# Shield_WDT.net
KiCad netlist of a schematic drawn in EasyEDA
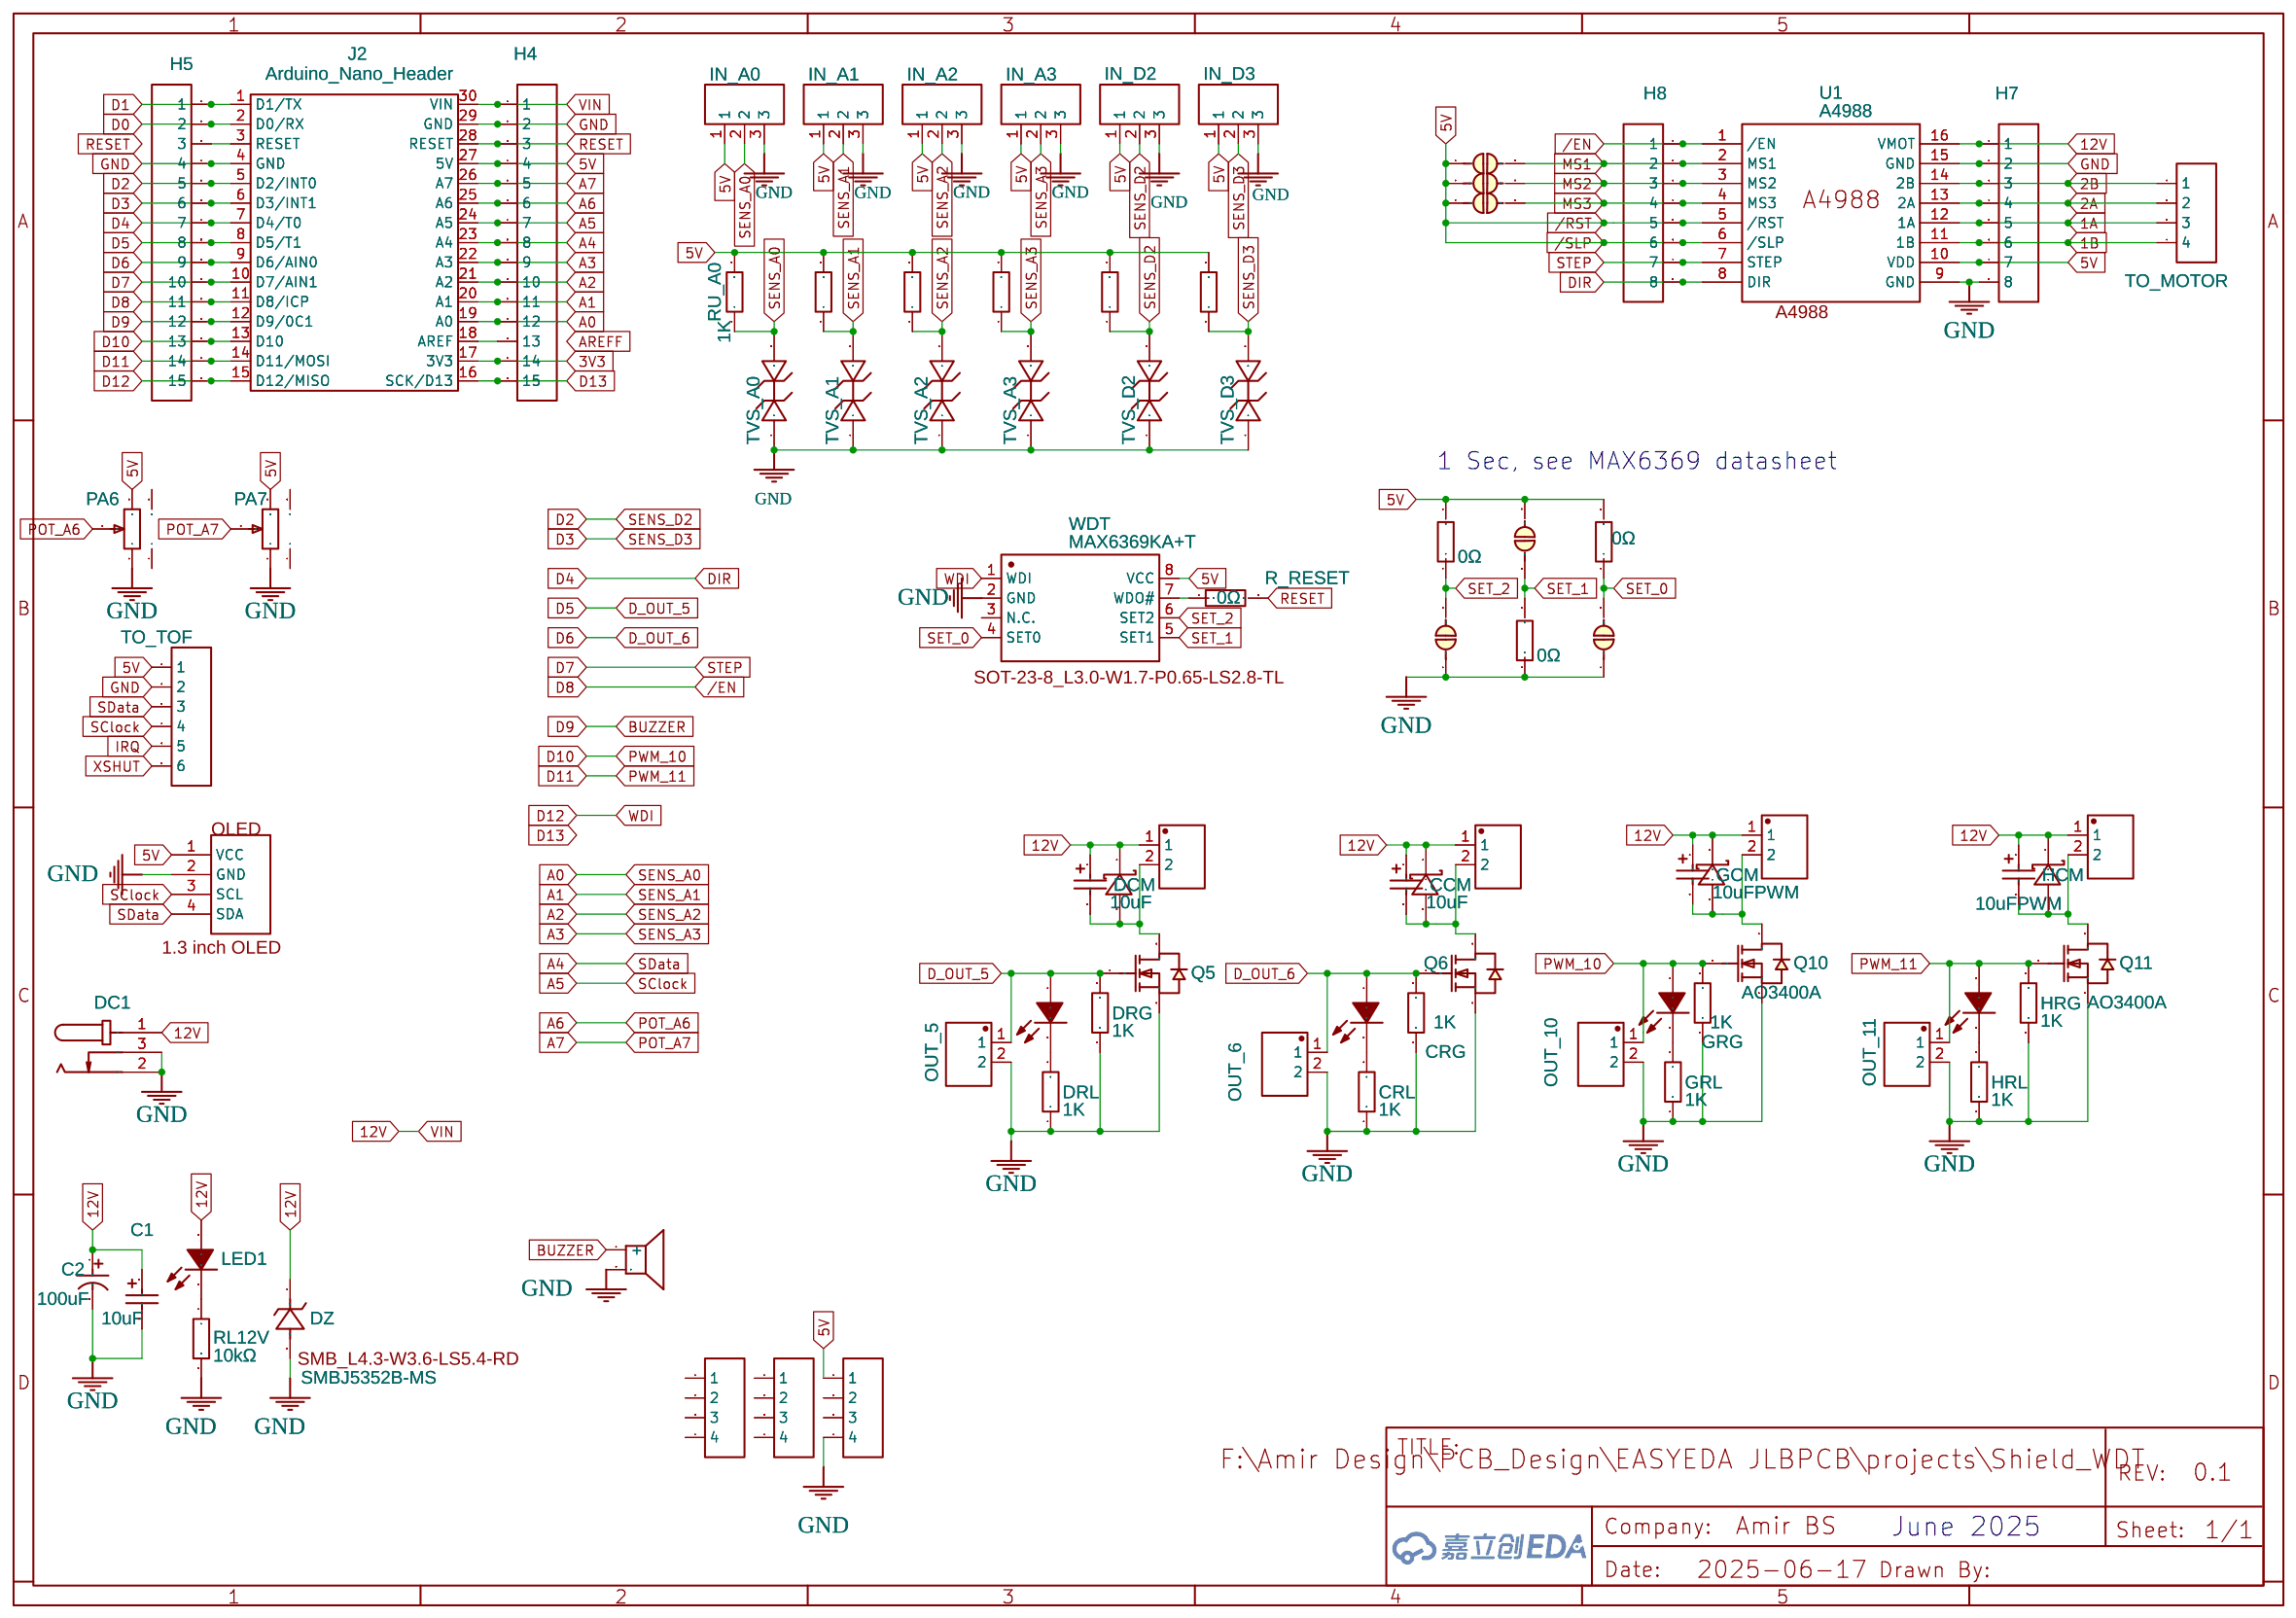
[diagram p0: schematic sheet]

(export (version "E")
  (design (tool "Eeschema 10.0.6"))
  (components
    (comp (ref "BUZZER1") (value "BUZZER-12X9") (libsource (lib "") (part "BUZZER-12X9")))
    (comp (ref "C1")
      (value "10uF")
      (fields (field (name "Manufacturer") "Kyocera AVX"))
      (libsource (lib "") (part "TAJA106K016RNJ_2"))
    )
    (comp (ref "C2")
      (value "100uF")
      (fields (field (name "Manufacturer") "CX(承兴)"))
      (libsource (lib "") (part "100uF 35V 6.3*11"))
    )
    (comp (ref "CCM") (value "10uF") (libsource (lib "") (part "TAJA106K016RNJ_4")))
    (comp (ref "CCON")
      (value "KF2510-2A")
      (fields (field (name "Manufacturer") "BOOMELE"))
      (libsource (lib "") (part "KF2510-2A_4"))
    )
    (comp (ref "CRG")
      (value "1K")
      (fields (field (name "Manufacturer Part") "0603WAF1001T5E") (field (name "Manufacturer") "UniOhm"))
      (libsource (lib "") (part "0603WAF1001T5E_3"))
    )
    (comp (ref "CRL")
      (value "1K")
      (fields (field (name "Manufacturer Part") "0603WAF1001T5E") (field (name "Manufacturer") "UniOhm"))
      (libsource (lib "") (part "0603WAF1001T5E"))
    )
    (comp (ref "D5")
      (value "1N5819WS")
      (fields (field (name "Manufacturer") "Hottech(合科泰)"))
      (libsource (lib "") (part "1N5819WS"))
    )
    (comp (ref "D6")
      (value "1N5819WS")
      (fields (field (name "Manufacturer") "Hottech(合科泰)"))
      (libsource (lib "") (part "1N5819WS"))
    )
    (comp (ref "D10")
      (value "1N5819WS")
      (fields (field (name "Manufacturer") "Hottech(合科泰)"))
      (libsource (lib "") (part "1N5819WS"))
    )
    (comp (ref "D11")
      (value "1N5819WS")
      (fields (field (name "Manufacturer") "Hottech(合科泰)"))
      (libsource (lib "") (part "1N5819WS"))
    )
    (comp (ref "DC1")
      (value "DC")
      (fields (field (name "Manufacturer Part") "DC005-2.0MM") (field (name "Manufacturer") "SOFNG"))
      (libsource (lib "") (part "DC005-2.0MM"))
    )
    (comp (ref "DCM") (value "10uF") (libsource (lib "") (part "TAJA106K016RNJ")))
    (comp (ref "DCON")
      (value "KF2510-2A")
      (fields (field (name "Manufacturer") "BOOMELE"))
      (libsource (lib "") (part "KF2510-2A_3"))
    )
    (comp (ref "DRG")
      (value "1K")
      (fields (field (name "Manufacturer Part") "0603WAF1001T5E") (field (name "Manufacturer") "UniOhm"))
      (libsource (lib "") (part "0603WAF1001T5E_8"))
    )
    (comp (ref "DRL")
      (value "1K")
      (fields (field (name "Manufacturer Part") "0603WAF1001T5E") (field (name "Manufacturer") "UniOhm"))
      (libsource (lib "") (part "0603WAF1001T5E_7"))
    )
    (comp (ref "DZ")
      (value "SMBJ5352B-MS")
      (fields (field (name "Manufacturer") "MSKSEMI(美森科)"))
      (libsource (lib "") (part "SMBJ5352B-MS"))
    )
    (comp (ref "GCM") (value "10uFPWM") (libsource (lib "") (part "TAJA106K016RNJ_1")))
    (comp (ref "GCON")
      (value "KF2510-2A")
      (fields (field (name "Manufacturer") "BOOMELE"))
      (libsource (lib "") (part "KF2510-2A"))
    )
    (comp (ref "GRG")
      (value "1K")
      (fields (field (name "Manufacturer Part") "0603WAF1001T5E") (field (name "Manufacturer") "UniOhm"))
      (libsource (lib "") (part "0603WAF1001T5E_4"))
    )
    (comp (ref "GRL")
      (value "1K")
      (fields (field (name "Manufacturer Part") "0603WAF1001T5E") (field (name "Manufacturer") "UniOhm"))
      (libsource (lib "") (part "0603WAF1001T5E_6"))
    )
    (comp (ref "H1") (value "HDR-F-2.54_1x4") (libsource (lib "") (part "HDR-F-2.54_1x4")))
    (comp (ref "H2") (value "HDR-F-2.54_1x4") (libsource (lib "") (part "HDR-F-2.54_1x4")))
    (comp (ref "H3") (value "HDR-F-2.54_1x4") (libsource (lib "") (part "HDR-F-2.54_1x4")))
    (comp (ref "H4") (value "HDR-F-2.54_1x15") (libsource (lib "") (part "HDR-F-2.54_1x15")))
    (comp (ref "H5") (value "HDR-F-2.54_1x15") (libsource (lib "") (part "HDR-F-2.54_1x15_1")))
    (comp (ref "H7") (value "HDR-F-2.54_1x8") (libsource (lib "") (part "HDR-F-2.54_1x8_1")))
    (comp (ref "H8") (value "HDR-F-2.54_1x8") (libsource (lib "") (part "HDR-F-2.54_1x8")))
    (comp (ref "HCM") (value "10uFPWM") (libsource (lib "") (part "TAJA106K016RNJ_3")))
    (comp (ref "HCON")
      (value "KF2510-2A")
      (fields (field (name "Manufacturer") "BOOMELE"))
      (libsource (lib "") (part "KF2510-2A_1"))
    )
    (comp (ref "HRG")
      (value "1K")
      (fields (field (name "Manufacturer Part") "0603WAF1001T5E") (field (name "Manufacturer") "UniOhm"))
      (libsource (lib "") (part "0603WAF1001T5E_9"))
    )
    (comp (ref "HRL")
      (value "1K")
      (fields (field (name "Manufacturer Part") "0603WAF1001T5E") (field (name "Manufacturer") "UniOhm"))
      (libsource (lib "") (part "0603WAF1001T5E_2"))
    )
    (comp (ref "IN_A0") (value "FK2510") (libsource (lib "") (part "kf2510_3A_1")))
    (comp (ref "IN_A1") (value "FK2510") (libsource (lib "") (part "kf2510_3A_1")))
    (comp (ref "IN_A2") (value "FK2510") (libsource (lib "") (part "kf2510_3A_1")))
    (comp (ref "IN_A3") (value "FK2510") (libsource (lib "") (part "kf2510_3A_1")))
    (comp (ref "IN_D2") (value "FK2510") (libsource (lib "") (part "kf2510_3A")))
    (comp (ref "IN_D3") (value "FK2510") (libsource (lib "") (part "kf2510_3A")))
    (comp (ref "J2") (value "Arduino_Nano_Header") (libsource (lib "") (part "Arduino_Nano_Header")))
    (comp (ref "JP1") (value "JUMPER-SMT_2") (libsource (lib "") (part "JUMPER-SMT_2_1")))
    (comp (ref "JP2") (value "JUMPER-SMT_2") (libsource (lib "") (part "JUMPER-SMT_2_1")))
    (comp (ref "JP3") (value "JUMPER-SMT_2") (libsource (lib "") (part "JUMPER-SMT_2_1")))
    (comp (ref "J_S0") (value "J_SET0") (libsource (lib "") (part "JUMPER-SMT_2")))
    (comp (ref "J_S1") (value "J_SET1") (libsource (lib "") (part "JUMPER-SMT_2")))
    (comp (ref "J_S2") (value "J_SET_2") (libsource (lib "") (part "JUMPER-SMT_2")))
    (comp (ref "LED1")
      (value "KT-0603R")
      (fields (field (name "Manufacturer") "KENTO"))
      (libsource (lib "") (part "KT-0603R"))
    )
    (comp (ref "LED5")
      (value "0603White light_C2290")
      (fields (field (name "Manufacturer") "KENTO"))
      (libsource (lib "") (part "0603White light_C2290"))
    )
    (comp (ref "LED6")
      (value "0603White light_C2290")
      (fields (field (name "Manufacturer") "KENTO"))
      (libsource (lib "") (part "0603White light_C2290"))
    )
    (comp (ref "LED10")
      (value "0603White light_C2290")
      (fields (field (name "Manufacturer") "KENTO"))
      (libsource (lib "") (part "0603White light_C2290"))
    )
    (comp (ref "LED11")
      (value "0603White light_C2290")
      (fields (field (name "Manufacturer") "KENTO"))
      (libsource (lib "") (part "0603White light_C2290"))
    )
    (comp (ref "OLED") (value "OLED_1_3_NO_HOLES") (libsource (lib "") (part "OLED_1_3_NO_HOLES")))
    (comp (ref "OUT_5")
      (value "KF2510-2A")
      (fields (field (name "Manufacturer") "BOOMELE"))
      (libsource (lib "") (part "KF2510-2A_2"))
    )
    (comp (ref "OUT_6")
      (value "KF2510-2A")
      (fields (field (name "Manufacturer") "BOOMELE"))
      (libsource (lib "") (part "KF2510-2A_2"))
    )
    (comp (ref "OUT_10")
      (value "KF2510-2A")
      (fields (field (name "Manufacturer") "BOOMELE"))
      (libsource (lib "") (part "KF2510-2A_2"))
    )
    (comp (ref "OUT_11")
      (value "KF2510-2A")
      (fields (field (name "Manufacturer") "BOOMELE"))
      (libsource (lib "") (part "KF2510-2A_2"))
    )
    (comp (ref "PA6") (value "长柄旋转电位器") (libsource (lib "") (part "长柄旋转电位器")))
    (comp (ref "PA7") (value "长柄旋转电位器") (libsource (lib "") (part "长柄旋转电位器")))
    (comp (ref "Q5")
      (value "AO3400A")
      (fields (field (name "Manufacturer") "AOS"))
      (libsource (lib "") (part "AO3400A"))
    )
    (comp (ref "Q6")
      (value "AO3400A")
      (fields (field (name "Manufacturer") "AOS"))
      (libsource (lib "") (part "AO3400A"))
    )
    (comp (ref "Q10")
      (value "AO3400A")
      (fields (field (name "Manufacturer") "AOS"))
      (libsource (lib "") (part "AO3400A"))
    )
    (comp (ref "Q11")
      (value "AO3400A")
      (fields (field (name "Manufacturer") "AOS"))
      (libsource (lib "") (part "AO3400A"))
    )
    (comp (ref "RL12V")
      (value "10kΩ")
      (fields
        (field (name "Manufacturer Part") "0603WAF1002T5E")
        (field (name "Manufacturer") "UNI-ROYAL(厚声)")
      )
      (libsource (lib "") (part "0603WAF1002T5E"))
    )
    (comp (ref "RU_A0")
      (value "1K")
      (fields (field (name "Manufacturer Part") "0603WAF1001T5E") (field (name "Manufacturer") "UniOhm"))
      (libsource (lib "") (part "0603WAF1001T5E_1"))
    )
    (comp (ref "RU_A1")
      (value "1K")
      (fields (field (name "Manufacturer Part") "0603WAF1001T5E") (field (name "Manufacturer") "UniOhm"))
      (libsource (lib "") (part "0603WAF1001T5E_1"))
    )
    (comp (ref "RU_A2")
      (value "1K")
      (fields (field (name "Manufacturer Part") "0603WAF1001T5E") (field (name "Manufacturer") "UniOhm"))
      (libsource (lib "") (part "0603WAF1001T5E_1"))
    )
    (comp (ref "RU_A3")
      (value "1K")
      (fields (field (name "Manufacturer Part") "0603WAF1001T5E") (field (name "Manufacturer") "UniOhm"))
      (libsource (lib "") (part "0603WAF1001T5E_1"))
    )
    (comp (ref "RU_D2")
      (value "1K")
      (fields (field (name "Manufacturer Part") "0603WAF1001T5E") (field (name "Manufacturer") "UniOhm"))
      (libsource (lib "") (part "0603WAF1001T5E_5"))
    )
    (comp (ref "RU_D3")
      (value "1K")
      (fields (field (name "Manufacturer Part") "0603WAF1001T5E") (field (name "Manufacturer") "UniOhm"))
      (libsource (lib "") (part "0603WAF1001T5E_5"))
    )
    (comp (ref "R_RESET")
      (value "0Ω")
      (fields (field (name "Manufacturer Part") "0402WGF0000TCE") (field (name "Manufacturer") "UniOhm"))
      (libsource (lib "") (part "0402WGF0000TCE_1"))
    )
    (comp (ref "R_S0")
      (value "0Ω")
      (fields (field (name "Manufacturer Part") "0402WGF0000TCE") (field (name "Manufacturer") "UniOhm"))
      (libsource (lib "") (part "0402WGF0000TCE"))
    )
    (comp (ref "R_S1")
      (value "0Ω")
      (fields (field (name "Manufacturer Part") "0402WGF0000TCE") (field (name "Manufacturer") "UniOhm"))
      (libsource (lib "") (part "0402WGF0000TCE"))
    )
    (comp (ref "R_S2")
      (value "0Ω")
      (fields (field (name "Manufacturer Part") "0402WGF0000TCE") (field (name "Manufacturer") "UniOhm"))
      (libsource (lib "") (part "0402WGF0000TCE"))
    )
    (comp (ref "TO_MOTOR") (value "HDR-F-2.54_1x4") (libsource (lib "") (part "HDR-F-2.54_1x4_1")))
    (comp (ref "TO_TOF") (value "HDR-F-2.54_1x6") (libsource (lib "") (part "HDR-F-2.54_1x6")))
    (comp (ref "TVS_A0")
      (value "TVSS5VCES-02GP-J")
      (fields (field (name "Manufacturer") "SINO-IC(光宇睿芯)"))
      (libsource (lib "") (part "TVSS5VCES-02GP-J"))
    )
    (comp (ref "TVS_A1")
      (value "TVSS5VCES-02GP-J")
      (fields (field (name "Manufacturer") "SINO-IC(光宇睿芯)"))
      (libsource (lib "") (part "TVSS5VCES-02GP-J"))
    )
    (comp (ref "TVS_A2")
      (value "TVSS5VCES-02GP-J")
      (fields (field (name "Manufacturer") "SINO-IC(光宇睿芯)"))
      (libsource (lib "") (part "TVSS5VCES-02GP-J"))
    )
    (comp (ref "TVS_A3")
      (value "TVSS5VCES-02GP-J")
      (fields (field (name "Manufacturer") "SINO-IC(光宇睿芯)"))
      (libsource (lib "") (part "TVSS5VCES-02GP-J"))
    )
    (comp (ref "TVS_D2")
      (value "TVSS5VCES-02GP-J")
      (fields (field (name "Manufacturer") "SINO-IC(光宇睿芯)"))
      (libsource (lib "") (part "TVSS5VCES-02GP-J_1"))
    )
    (comp (ref "TVS_D3")
      (value "TVSS5VCES-02GP-J")
      (fields (field (name "Manufacturer") "SINO-IC(光宇睿芯)"))
      (libsource (lib "") (part "TVSS5VCES-02GP-J_1"))
    )
    (comp (ref "U1") (value "A4988") (libsource (lib "") (part "A4988")))
    (comp (ref "WDT")
      (value "MAX6369KA+T")
      (fields (field (name "Manufacturer") "ADI(亚德诺)/MAXIM(美信)"))
      (libsource (lib "") (part "MAX6369KA+T"))
    )
  )
  (nets
    (net (code "1") (name "1A") (class "Default")
      (node (ref "H7") (pin "5") (pinfunction "5_5") (pintype "unspecified"))
      (node (ref "TO_MOTOR") (pin "3") (pinfunction "3_3") (pintype "unspecified"))
      (node (ref "U1") (pin "12") (pinfunction "1A_12") (pintype "unspecified"))
    )
    (net (code "2") (name "1B") (class "Default")
      (node (ref "H7") (pin "6") (pinfunction "6_6") (pintype "unspecified"))
      (node (ref "TO_MOTOR") (pin "4") (pinfunction "4_4") (pintype "unspecified"))
      (node (ref "U1") (pin "11") (pinfunction "1B_11") (pintype "unspecified"))
    )
    (net (code "3") (name "2A") (class "Default")
      (node (ref "H7") (pin "4") (pinfunction "4_4") (pintype "unspecified"))
      (node (ref "TO_MOTOR") (pin "2") (pinfunction "2_2") (pintype "unspecified"))
      (node (ref "U1") (pin "13") (pinfunction "2A_13") (pintype "unspecified"))
    )
    (net (code "4") (name "2B") (class "Default")
      (node (ref "H7") (pin "3") (pinfunction "3_3") (pintype "unspecified"))
      (node (ref "TO_MOTOR") (pin "1") (pinfunction "1_1") (pintype "unspecified"))
      (node (ref "U1") (pin "14") (pinfunction "2B_14") (pintype "unspecified"))
    )
    (net (code "5") (name "3V3") (class "Default")
      (node (ref "H4") (pin "14") (pinfunction "14_14") (pintype "unspecified"))
      (node (ref "J2") (pin "17") (pinfunction "3V3_17") (pintype "unspecified"))
    )
    (net (code "6") (name "5V") (class "Default")
      (node (ref "H3") (pin "1") (pinfunction "1_1") (pintype "unspecified"))
      (node (ref "H4") (pin "4") (pinfunction "4_4") (pintype "unspecified"))
      (node (ref "H7") (pin "7") (pinfunction "7_7") (pintype "unspecified"))
      (node (ref "H8") (pin "5") (pinfunction "5_5") (pintype "unspecified"))
      (node (ref "H8") (pin "6") (pinfunction "6_6") (pintype "unspecified"))
      (node (ref "IN_A0") (pin "1") (pinfunction "1_1") (pintype "unspecified"))
      (node (ref "IN_A1") (pin "1") (pinfunction "1_1") (pintype "unspecified"))
      (node (ref "IN_A2") (pin "1") (pinfunction "1_1") (pintype "unspecified"))
      (node (ref "IN_A3") (pin "1") (pinfunction "1_1") (pintype "unspecified"))
      (node (ref "IN_D2") (pin "1") (pinfunction "1_1") (pintype "unspecified"))
      (node (ref "IN_D3") (pin "1") (pinfunction "1_1") (pintype "unspecified"))
      (node (ref "J2") (pin "27") (pinfunction "5V_27") (pintype "unspecified"))
      (node (ref "JP1") (pin "1") (pinfunction "1_1") (pintype "bidirectional"))
      (node (ref "JP2") (pin "1") (pinfunction "1_1") (pintype "bidirectional"))
      (node (ref "JP3") (pin "1") (pinfunction "1_1") (pintype "bidirectional"))
      (node (ref "J_S1") (pin "2") (pinfunction "2_2") (pintype "bidirectional"))
      (node (ref "OLED") (pin "1") (pinfunction "VCC_1") (pintype "passive"))
      (node (ref "PA6") (pin "3") (pinfunction "3_3") (pintype "input"))
      (node (ref "PA7") (pin "3") (pinfunction "3_3") (pintype "input"))
      (node (ref "RU_A0") (pin "2") (pinfunction "2_2") (pintype "input"))
      (node (ref "RU_A1") (pin "2") (pinfunction "2_2") (pintype "input"))
      (node (ref "RU_A2") (pin "2") (pinfunction "2_2") (pintype "input"))
      (node (ref "RU_A3") (pin "2") (pinfunction "2_2") (pintype "input"))
      (node (ref "RU_D2") (pin "2") (pinfunction "2_2") (pintype "input"))
      (node (ref "RU_D3") (pin "2") (pinfunction "2_2") (pintype "input"))
      (node (ref "R_S0") (pin "2") (pinfunction "2_2") (pintype "input"))
      (node (ref "R_S2") (pin "2") (pinfunction "2_2") (pintype "input"))
      (node (ref "TO_TOF") (pin "1") (pinfunction "1_1") (pintype "input"))
      (node (ref "U1") (pin "10") (pinfunction "VDD_10") (pintype "unspecified"))
      (node (ref "U1") (pin "5") (pinfunction "/RST_5") (pintype "unspecified"))
      (node (ref "U1") (pin "6") (pinfunction "/SLP_6") (pintype "unspecified"))
      (node (ref "WDT") (pin "8") (pinfunction "VCC_8") (pintype "unspecified"))
    )
    (net (code "7") (name "12V") (class "Default")
      (node (ref "C1") (pin "1") (pinfunction "1_1") (pintype "input"))
      (node (ref "C2") (pin "1") (pinfunction "1_1") (pintype "input"))
      (node (ref "CCM") (pin "1") (pinfunction "1_1") (pintype "input"))
      (node (ref "CCON") (pin "1") (pinfunction "1_1") (pintype "unspecified"))
      (node (ref "D10") (pin "1") (pinfunction "K_1") (pintype "unspecified"))
      (node (ref "D11") (pin "1") (pinfunction "K_1") (pintype "unspecified"))
      (node (ref "D5") (pin "1") (pinfunction "K_1") (pintype "unspecified"))
      (node (ref "D6") (pin "1") (pinfunction "K_1") (pintype "unspecified"))
      (node (ref "DC1") (pin "1") (pinfunction "1_1") (pintype "unspecified"))
      (node (ref "DCM") (pin "1") (pinfunction "1_1") (pintype "input"))
      (node (ref "DCON") (pin "1") (pinfunction "1_1") (pintype "unspecified"))
      (node (ref "DZ") (pin "1") (pinfunction "K_1") (pintype "unspecified"))
      (node (ref "GCM") (pin "1") (pinfunction "1_1") (pintype "input"))
      (node (ref "GCON") (pin "1") (pinfunction "1_1") (pintype "unspecified"))
      (node (ref "H4") (pin "1") (pinfunction "1_1") (pintype "unspecified"))
      (node (ref "H7") (pin "1") (pinfunction "1_1") (pintype "unspecified"))
      (node (ref "HCM") (pin "1") (pinfunction "1_1") (pintype "input"))
      (node (ref "HCON") (pin "1") (pinfunction "1_1") (pintype "unspecified"))
      (node (ref "J2") (pin "30") (pinfunction "VIN_30") (pintype "unspecified"))
      (node (ref "LED1") (pin "2") (pinfunction "A_2") (pintype "unspecified"))
      (node (ref "U1") (pin "16") (pinfunction "VMOT_16") (pintype "unspecified"))
    )
    (net (code "8") (name "A0") (class "Default")
      (node (ref "H4") (pin "12") (pinfunction "12_12") (pintype "unspecified"))
      (node (ref "IN_A0") (pin "2") (pinfunction "2_2") (pintype "unspecified"))
      (node (ref "J2") (pin "19") (pinfunction "A0_19") (pintype "unspecified"))
      (node (ref "RU_A0") (pin "1") (pinfunction "1_1") (pintype "input"))
      (node (ref "TVS_A0") (pin "2") (pinfunction "2_2") (pintype "unspecified"))
    )
    (net (code "9") (name "A1") (class "Default")
      (node (ref "H4") (pin "11") (pinfunction "11_11") (pintype "unspecified"))
      (node (ref "IN_A1") (pin "2") (pinfunction "2_2") (pintype "unspecified"))
      (node (ref "J2") (pin "20") (pinfunction "A1_20") (pintype "unspecified"))
      (node (ref "RU_A1") (pin "1") (pinfunction "1_1") (pintype "input"))
      (node (ref "TVS_A1") (pin "2") (pinfunction "2_2") (pintype "unspecified"))
    )
    (net (code "10") (name "A2") (class "Default")
      (node (ref "H4") (pin "10") (pinfunction "10_10") (pintype "unspecified"))
      (node (ref "IN_A2") (pin "2") (pinfunction "2_2") (pintype "unspecified"))
      (node (ref "J2") (pin "21") (pinfunction "A2_21") (pintype "unspecified"))
      (node (ref "RU_A2") (pin "1") (pinfunction "1_1") (pintype "input"))
      (node (ref "TVS_A2") (pin "2") (pinfunction "2_2") (pintype "unspecified"))
    )
    (net (code "11") (name "A3") (class "Default")
      (node (ref "H4") (pin "9") (pinfunction "9_9") (pintype "unspecified"))
      (node (ref "IN_A3") (pin "2") (pinfunction "2_2") (pintype "unspecified"))
      (node (ref "J2") (pin "22") (pinfunction "A3_22") (pintype "unspecified"))
      (node (ref "RU_A3") (pin "1") (pinfunction "1_1") (pintype "input"))
      (node (ref "TVS_A3") (pin "2") (pinfunction "2_2") (pintype "unspecified"))
    )
    (net (code "12") (name "A4") (class "Default")
      (node (ref "H4") (pin "8") (pinfunction "8_8") (pintype "unspecified"))
      (node (ref "J2") (pin "23") (pinfunction "A4_23") (pintype "unspecified"))
      (node (ref "OLED") (pin "4") (pinfunction "SDA_4") (pintype "bidirectional"))
      (node (ref "TO_TOF") (pin "3") (pinfunction "3_3") (pintype "input"))
    )
    (net (code "13") (name "A5") (class "Default")
      (node (ref "H4") (pin "7") (pinfunction "7_7") (pintype "unspecified"))
      (node (ref "J2") (pin "24") (pinfunction "A5_24") (pintype "unspecified"))
      (node (ref "OLED") (pin "3") (pinfunction "SCL_3") (pintype "bidirectional"))
      (node (ref "TO_TOF") (pin "4") (pinfunction "4_4") (pintype "input"))
    )
    (net (code "14") (name "A6") (class "Default")
      (node (ref "H4") (pin "6") (pinfunction "6_6") (pintype "unspecified"))
      (node (ref "J2") (pin "25") (pinfunction "A6_25") (pintype "unspecified"))
      (node (ref "PA6") (pin "2") (pinfunction "2_2") (pintype "input"))
    )
    (net (code "15") (name "A7") (class "Default")
      (node (ref "H4") (pin "5") (pinfunction "5_5") (pintype "unspecified"))
      (node (ref "J2") (pin "26") (pinfunction "A7_26") (pintype "unspecified"))
      (node (ref "PA7") (pin "2") (pinfunction "2_2") (pintype "input"))
    )
    (net (code "17") (name "BUZZER") (class "Default")
      (node (ref "BUZZER1") (pin "1") (pinfunction "+_1") (pintype "unspecified"))
      (node (ref "H5") (pin "12") (pinfunction "12_12") (pintype "unspecified"))
      (node (ref "J2") (pin "12") (pinfunction "D9/0C1_12") (pintype "unspecified"))
    )
    (net (code "18") (name "D0") (class "Default")
      (node (ref "H5") (pin "2") (pinfunction "2_2") (pintype "unspecified"))
      (node (ref "J2") (pin "2") (pinfunction "D0/RX_2") (pintype "unspecified"))
    )
    (net (code "19") (name "D1") (class "Default")
      (node (ref "H5") (pin "1") (pinfunction "1_1") (pintype "unspecified"))
      (node (ref "J2") (pin "1") (pinfunction "D1/TX_1") (pintype "unspecified"))
    )
    (net (code "20") (name "D2") (class "Default")
      (node (ref "H5") (pin "5") (pinfunction "5_5") (pintype "unspecified"))
      (node (ref "IN_D2") (pin "2") (pinfunction "2_2") (pintype "unspecified"))
      (node (ref "J2") (pin "5") (pinfunction "D2/INT0_5") (pintype "unspecified"))
      (node (ref "RU_D2") (pin "1") (pinfunction "1_1") (pintype "input"))
      (node (ref "TVS_D2") (pin "2") (pinfunction "2_2") (pintype "unspecified"))
    )
    (net (code "21") (name "D3") (class "Default")
      (node (ref "H5") (pin "6") (pinfunction "6_6") (pintype "unspecified"))
      (node (ref "IN_D3") (pin "2") (pinfunction "2_2") (pintype "unspecified"))
      (node (ref "J2") (pin "6") (pinfunction "D3/INT1_6") (pintype "unspecified"))
      (node (ref "RU_D3") (pin "1") (pinfunction "1_1") (pintype "input"))
      (node (ref "TVS_D3") (pin "2") (pinfunction "2_2") (pintype "unspecified"))
    )
    (net (code "22") (name "D4") (class "Default")
      (node (ref "H5") (pin "7") (pinfunction "7_7") (pintype "unspecified"))
      (node (ref "H8") (pin "8") (pinfunction "8_8") (pintype "unspecified"))
      (node (ref "J2") (pin "7") (pinfunction "D4/T0_7") (pintype "unspecified"))
      (node (ref "U1") (pin "8") (pinfunction "DIR_8") (pintype "unspecified"))
    )
    (net (code "23") (name "D5") (class "Default")
      (node (ref "DRG") (pin "2") (pinfunction "2_2") (pintype "input"))
      (node (ref "H5") (pin "8") (pinfunction "8_8") (pintype "unspecified"))
      (node (ref "J2") (pin "8") (pinfunction "D5/T1_8") (pintype "unspecified"))
      (node (ref "LED5") (pin "1") (pinfunction "A_1") (pintype "unspecified"))
      (node (ref "OUT_5") (pin "1") (pinfunction "1_1") (pintype "unspecified"))
      (node (ref "Q5") (pin "1") (pinfunction "G_1") (pintype "unspecified"))
    )
    (net (code "24") (name "D6") (class "Default")
      (node (ref "CRG") (pin "2") (pinfunction "2_2") (pintype "input"))
      (node (ref "H5") (pin "9") (pinfunction "9_9") (pintype "unspecified"))
      (node (ref "J2") (pin "9") (pinfunction "D6/AIN0_9") (pintype "unspecified"))
      (node (ref "LED6") (pin "1") (pinfunction "A_1") (pintype "unspecified"))
      (node (ref "OUT_6") (pin "1") (pinfunction "1_1") (pintype "unspecified"))
      (node (ref "Q6") (pin "1") (pinfunction "G_1") (pintype "unspecified"))
    )
    (net (code "25") (name "D7") (class "Default")
      (node (ref "H5") (pin "10") (pinfunction "10_10") (pintype "unspecified"))
      (node (ref "H8") (pin "7") (pinfunction "7_7") (pintype "unspecified"))
      (node (ref "J2") (pin "10") (pinfunction "D7/AIN1_10") (pintype "unspecified"))
      (node (ref "U1") (pin "7") (pinfunction "STEP_7") (pintype "unspecified"))
    )
    (net (code "26") (name "D8") (class "Default")
      (node (ref "H5") (pin "11") (pinfunction "11_11") (pintype "unspecified"))
      (node (ref "H8") (pin "1") (pinfunction "1_1") (pintype "unspecified"))
      (node (ref "J2") (pin "11") (pinfunction "D8/ICP_11") (pintype "unspecified"))
      (node (ref "U1") (pin "1") (pinfunction "/EN_1") (pintype "unspecified"))
    )
    (net (code "27") (name "D10") (class "Default")
      (node (ref "GRG") (pin "2") (pinfunction "2_2") (pintype "input"))
      (node (ref "H5") (pin "13") (pinfunction "13_13") (pintype "unspecified"))
      (node (ref "J2") (pin "13") (pinfunction "D10_13") (pintype "unspecified"))
      (node (ref "LED10") (pin "1") (pinfunction "A_1") (pintype "unspecified"))
      (node (ref "OUT_10") (pin "1") (pinfunction "1_1") (pintype "unspecified"))
      (node (ref "Q10") (pin "1") (pinfunction "G_1") (pintype "unspecified"))
    )
    (net (code "28") (name "D11") (class "Default")
      (node (ref "H5") (pin "14") (pinfunction "14_14") (pintype "unspecified"))
      (node (ref "HRG") (pin "2") (pinfunction "2_2") (pintype "input"))
      (node (ref "J2") (pin "14") (pinfunction "D11/MOSI_14") (pintype "unspecified"))
      (node (ref "LED11") (pin "1") (pinfunction "A_1") (pintype "unspecified"))
      (node (ref "OUT_11") (pin "1") (pinfunction "1_1") (pintype "unspecified"))
      (node (ref "Q11") (pin "1") (pinfunction "G_1") (pintype "unspecified"))
    )
    (net (code "29") (name "D12") (class "Default")
      (node (ref "H5") (pin "15") (pinfunction "15_15") (pintype "unspecified"))
      (node (ref "J2") (pin "15") (pinfunction "D12/MISO_15") (pintype "unspecified"))
      (node (ref "WDT") (pin "1") (pinfunction "WDI_1") (pintype "unspecified"))
    )
    (net (code "30") (name "D13") (class "Default")
      (node (ref "H4") (pin "15") (pinfunction "15_15") (pintype "unspecified"))
      (node (ref "J2") (pin "16") (pinfunction "SCK/D13_16") (pintype "unspecified"))
    )
    (net (code "31") (name "GND") (class "Default")
      (node (ref "BUZZER1") (pin "2") (pinfunction "2_2") (pintype "unspecified"))
      (node (ref "C1") (pin "2") (pinfunction "2_2") (pintype "input"))
      (node (ref "C2") (pin "2") (pinfunction "2_2") (pintype "input"))
      (node (ref "CRG") (pin "1") (pinfunction "1_1") (pintype "input"))
      (node (ref "CRL") (pin "1") (pinfunction "1_1") (pintype "input"))
      (node (ref "DC1") (pin "2") (pinfunction "2_2") (pintype "unspecified"))
      (node (ref "DC1") (pin "3") (pinfunction "3_3") (pintype "unspecified"))
      (node (ref "DRG") (pin "1") (pinfunction "1_1") (pintype "input"))
      (node (ref "DRL") (pin "1") (pinfunction "1_1") (pintype "input"))
      (node (ref "DZ") (pin "2") (pinfunction "A_2") (pintype "unspecified"))
      (node (ref "GRG") (pin "1") (pinfunction "1_1") (pintype "input"))
      (node (ref "GRL") (pin "1") (pinfunction "1_1") (pintype "input"))
      (node (ref "H3") (pin "4") (pinfunction "4_4") (pintype "unspecified"))
      (node (ref "H4") (pin "2") (pinfunction "2_2") (pintype "unspecified"))
      (node (ref "H5") (pin "4") (pinfunction "4_4") (pintype "unspecified"))
      (node (ref "H7") (pin "2") (pinfunction "2_2") (pintype "unspecified"))
      (node (ref "H7") (pin "8") (pinfunction "8_8") (pintype "unspecified"))
      (node (ref "HRG") (pin "1") (pinfunction "1_1") (pintype "input"))
      (node (ref "HRL") (pin "1") (pinfunction "1_1") (pintype "input"))
      (node (ref "IN_A0") (pin "3") (pinfunction "3_3") (pintype "unspecified"))
      (node (ref "IN_A1") (pin "3") (pinfunction "3_3") (pintype "unspecified"))
      (node (ref "IN_A2") (pin "3") (pinfunction "3_3") (pintype "unspecified"))
      (node (ref "IN_A3") (pin "3") (pinfunction "3_3") (pintype "unspecified"))
      (node (ref "IN_D2") (pin "3") (pinfunction "3_3") (pintype "unspecified"))
      (node (ref "IN_D3") (pin "3") (pinfunction "3_3") (pintype "unspecified"))
      (node (ref "J2") (pin "29") (pinfunction "GND_29") (pintype "unspecified"))
      (node (ref "J2") (pin "4") (pinfunction "GND_4") (pintype "unspecified"))
      (node (ref "J_S0") (pin "1") (pinfunction "1_1") (pintype "bidirectional"))
      (node (ref "J_S2") (pin "1") (pinfunction "1_1") (pintype "bidirectional"))
      (node (ref "OLED") (pin "2") (pinfunction "GND_2") (pintype "passive"))
      (node (ref "OUT_10") (pin "2") (pinfunction "2_2") (pintype "unspecified"))
      (node (ref "OUT_11") (pin "2") (pinfunction "2_2") (pintype "unspecified"))
      (node (ref "OUT_5") (pin "2") (pinfunction "2_2") (pintype "unspecified"))
      (node (ref "OUT_6") (pin "2") (pinfunction "2_2") (pintype "unspecified"))
      (node (ref "PA6") (pin "1") (pinfunction "1_1") (pintype "input"))
      (node (ref "PA7") (pin "1") (pinfunction "1_1") (pintype "input"))
      (node (ref "Q10") (pin "2") (pinfunction "S_2") (pintype "unspecified"))
      (node (ref "Q11") (pin "2") (pinfunction "S_2") (pintype "unspecified"))
      (node (ref "Q5") (pin "2") (pinfunction "S_2") (pintype "unspecified"))
      (node (ref "Q6") (pin "2") (pinfunction "S_2") (pintype "unspecified"))
      (node (ref "RL12V") (pin "2") (pinfunction "2_2") (pintype "input"))
      (node (ref "R_S1") (pin "1") (pinfunction "1_1") (pintype "input"))
      (node (ref "TO_TOF") (pin "2") (pinfunction "2_2") (pintype "input"))
      (node (ref "TVS_A0") (pin "1") (pinfunction "1_1") (pintype "unspecified"))
      (node (ref "TVS_A1") (pin "1") (pinfunction "1_1") (pintype "unspecified"))
      (node (ref "TVS_A2") (pin "1") (pinfunction "1_1") (pintype "unspecified"))
      (node (ref "TVS_A3") (pin "1") (pinfunction "1_1") (pintype "unspecified"))
      (node (ref "TVS_D2") (pin "1") (pinfunction "1_1") (pintype "unspecified"))
      (node (ref "TVS_D3") (pin "1") (pinfunction "1_1") (pintype "unspecified"))
      (node (ref "U1") (pin "15") (pinfunction "GND_15") (pintype "unspecified"))
      (node (ref "U1") (pin "9") (pinfunction "GND_9") (pintype "unspecified"))
      (node (ref "WDT") (pin "2") (pinfunction "GND_2") (pintype "unspecified"))
    )
    (net (code "32") (name "IRQ") (class "Default")
      (node (ref "TO_TOF") (pin "5") (pinfunction "5_5") (pintype "input"))
    )
    (net (code "33") (name "MS1") (class "Default")
      (node (ref "H8") (pin "2") (pinfunction "2_2") (pintype "unspecified"))
      (node (ref "JP1") (pin "2") (pinfunction "2_2") (pintype "bidirectional"))
      (node (ref "U1") (pin "2") (pinfunction "MS1_2") (pintype "unspecified"))
    )
    (net (code "34") (name "MS2") (class "Default")
      (node (ref "H8") (pin "3") (pinfunction "3_3") (pintype "unspecified"))
      (node (ref "JP2") (pin "2") (pinfunction "2_2") (pintype "bidirectional"))
      (node (ref "U1") (pin "3") (pinfunction "MS2_3") (pintype "unspecified"))
    )
    (net (code "35") (name "MS3") (class "Default")
      (node (ref "H8") (pin "4") (pinfunction "4_4") (pintype "unspecified"))
      (node (ref "JP3") (pin "2") (pinfunction "2_2") (pintype "bidirectional"))
      (node (ref "U1") (pin "4") (pinfunction "MS3_4") (pintype "unspecified"))
    )
    (net (code "36") (name "Net-(D5-A)") (class "Default")
      (node (ref "D5") (pin "2") (pinfunction "A_2") (pintype "unspecified"))
      (node (ref "DCM") (pin "2") (pinfunction "2_2") (pintype "input"))
      (node (ref "DCON") (pin "2") (pinfunction "2_2") (pintype "unspecified"))
      (node (ref "Q5") (pin "3") (pinfunction "D_3") (pintype "unspecified"))
    )
    (net (code "37") (name "Net-(D6-A)") (class "Default")
      (node (ref "CCM") (pin "2") (pinfunction "2_2") (pintype "input"))
      (node (ref "CCON") (pin "2") (pinfunction "2_2") (pintype "unspecified"))
      (node (ref "D6") (pin "2") (pinfunction "A_2") (pintype "unspecified"))
      (node (ref "Q6") (pin "3") (pinfunction "D_3") (pintype "unspecified"))
    )
    (net (code "38") (name "Net-(D10-A)") (class "Default")
      (node (ref "D10") (pin "2") (pinfunction "A_2") (pintype "unspecified"))
      (node (ref "GCM") (pin "2") (pinfunction "2_2") (pintype "input"))
      (node (ref "GCON") (pin "2") (pinfunction "2_2") (pintype "unspecified"))
      (node (ref "Q10") (pin "3") (pinfunction "D_3") (pintype "unspecified"))
    )
    (net (code "39") (name "Net-(D11-A)") (class "Default")
      (node (ref "D11") (pin "2") (pinfunction "A_2") (pintype "unspecified"))
      (node (ref "HCM") (pin "2") (pinfunction "2_2") (pintype "input"))
      (node (ref "HCON") (pin "2") (pinfunction "2_2") (pintype "unspecified"))
      (node (ref "Q11") (pin "3") (pinfunction "D_3") (pintype "unspecified"))
    )
    (net (code "40") (name "Net-(H5-Pad3)") (class "Default")
      (node (ref "H5") (pin "3") (pinfunction "3_3") (pintype "unspecified"))
      (node (ref "J2") (pin "3") (pinfunction "RESET_3") (pintype "unspecified"))
    )
    (net (code "41") (name "Net-(J2-AREF)") (class "Default")
      (node (ref "H4") (pin "13") (pinfunction "13_13") (pintype "unspecified"))
      (node (ref "J2") (pin "18") (pinfunction "AREF_18") (pintype "unspecified"))
    )
    (net (code "42") (name "Net-(LED1-K)") (class "Default")
      (node (ref "LED1") (pin "1") (pinfunction "K_1") (pintype "unspecified"))
      (node (ref "RL12V") (pin "1") (pinfunction "1_1") (pintype "input"))
    )
    (net (code "43") (name "Net-(LED5-K)") (class "Default")
      (node (ref "DRL") (pin "2") (pinfunction "2_2") (pintype "input"))
      (node (ref "LED5") (pin "2") (pinfunction "K_2") (pintype "unspecified"))
    )
    (net (code "44") (name "Net-(LED6-K)") (class "Default")
      (node (ref "CRL") (pin "2") (pinfunction "2_2") (pintype "input"))
      (node (ref "LED6") (pin "2") (pinfunction "K_2") (pintype "unspecified"))
    )
    (net (code "45") (name "Net-(LED10-K)") (class "Default")
      (node (ref "GRL") (pin "2") (pinfunction "2_2") (pintype "input"))
      (node (ref "LED10") (pin "2") (pinfunction "K_2") (pintype "unspecified"))
    )
    (net (code "46") (name "Net-(LED11-K)") (class "Default")
      (node (ref "HRL") (pin "2") (pinfunction "2_2") (pintype "input"))
      (node (ref "LED11") (pin "2") (pinfunction "K_2") (pintype "unspecified"))
    )
    (net (code "47") (name "Net-(WDT-WDO#)") (class "Default")
      (node (ref "R_RESET") (pin "1") (pinfunction "1_1") (pintype "input"))
      (node (ref "WDT") (pin "7") (pinfunction "WDO#_7") (pintype "unspecified"))
    )
    (net (code "48") (name "RESET") (class "Default")
      (node (ref "H4") (pin "3") (pinfunction "3_3") (pintype "unspecified"))
      (node (ref "J2") (pin "28") (pinfunction "RESET_28") (pintype "unspecified"))
      (node (ref "R_RESET") (pin "2") (pinfunction "2_2") (pintype "input"))
    )
    (net (code "49") (name "SET_0") (class "Default")
      (node (ref "J_S0") (pin "2") (pinfunction "2_2") (pintype "bidirectional"))
      (node (ref "R_S0") (pin "1") (pinfunction "1_1") (pintype "input"))
      (node (ref "WDT") (pin "4") (pinfunction "SET0_4") (pintype "unspecified"))
    )
    (net (code "50") (name "SET_1") (class "Default")
      (node (ref "J_S1") (pin "1") (pinfunction "1_1") (pintype "bidirectional"))
      (node (ref "R_S1") (pin "2") (pinfunction "2_2") (pintype "input"))
      (node (ref "WDT") (pin "5") (pinfunction "SET1_5") (pintype "unspecified"))
    )
    (net (code "51") (name "SET_2") (class "Default")
      (node (ref "J_S2") (pin "2") (pinfunction "2_2") (pintype "bidirectional"))
      (node (ref "R_S2") (pin "1") (pinfunction "1_1") (pintype "input"))
      (node (ref "WDT") (pin "6") (pinfunction "SET2_6") (pintype "unspecified"))
    )
    (net (code "52") (name "XSHUT") (class "Default")
      (node (ref "TO_TOF") (pin "6") (pinfunction "6_6") (pintype "input"))
    )
    (net (code "53") (name "unconnected-(H1-Pad1)") (class "Default")
      (node (ref "H1") (pin "1") (pinfunction "1_1") (pintype "unspecified"))
    )
    (net (code "54") (name "unconnected-(H1-Pad2)") (class "Default")
      (node (ref "H1") (pin "2") (pinfunction "2_2") (pintype "unspecified"))
    )
    (net (code "55") (name "unconnected-(H1-Pad3)") (class "Default")
      (node (ref "H1") (pin "3") (pinfunction "3_3") (pintype "unspecified"))
    )
    (net (code "56") (name "unconnected-(H1-Pad4)") (class "Default")
      (node (ref "H1") (pin "4") (pinfunction "4_4") (pintype "unspecified"))
    )
    (net (code "57") (name "unconnected-(H2-Pad1)") (class "Default")
      (node (ref "H2") (pin "1") (pinfunction "1_1") (pintype "unspecified"))
    )
    (net (code "58") (name "unconnected-(H2-Pad2)") (class "Default")
      (node (ref "H2") (pin "2") (pinfunction "2_2") (pintype "unspecified"))
    )
    (net (code "59") (name "unconnected-(H2-Pad3)") (class "Default")
      (node (ref "H2") (pin "3") (pinfunction "3_3") (pintype "unspecified"))
    )
    (net (code "60") (name "unconnected-(H2-Pad4)") (class "Default")
      (node (ref "H2") (pin "4") (pinfunction "4_4") (pintype "unspecified"))
    )
    (net (code "61") (name "unconnected-(H3-Pad2)") (class "Default")
      (node (ref "H3") (pin "2") (pinfunction "2_2") (pintype "unspecified"))
    )
    (net (code "62") (name "unconnected-(H3-Pad3)") (class "Default")
      (node (ref "H3") (pin "3") (pinfunction "3_3") (pintype "unspecified"))
    )
    (net (code "63") (name "unconnected-(PA6-Pad4)") (class "Default")
      (node (ref "PA6") (pin "4") (pinfunction "4_4") (pintype "input"))
    )
    (net (code "64") (name "unconnected-(PA6-Pad5)") (class "Default")
      (node (ref "PA6") (pin "5") (pinfunction "5_5") (pintype "input"))
    )
    (net (code "65") (name "unconnected-(PA7-Pad4)") (class "Default")
      (node (ref "PA7") (pin "4") (pinfunction "4_4") (pintype "input"))
    )
    (net (code "66") (name "unconnected-(PA7-Pad5)") (class "Default")
      (node (ref "PA7") (pin "5") (pinfunction "5_5") (pintype "input"))
    )
    (net (code "67") (name "unconnected-(WDT-N.C.-Pad3)") (class "Default")
      (node (ref "WDT") (pin "3") (pinfunction "N.C._3") (pintype "unspecified"))
    )
  )
)
